# 5vTemp.net
KiCad netlist of a schematic drawn in EAGLE
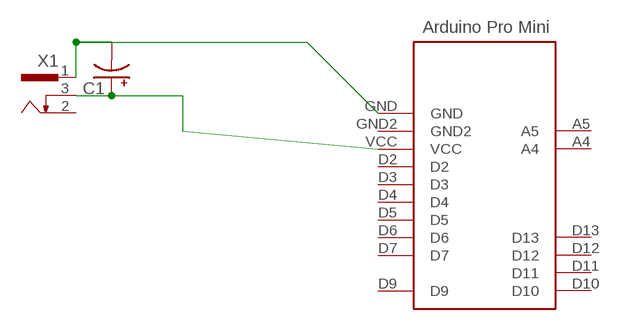
[diagram p0: schematic, sheet 1]

(export (version "E")
  (design (tool "Eeschema 10.0.6"))
  (components
    (comp (ref "C1")
      (value "CPOL-USSANYO_C")
      (footprint "eagle-import:SANYO-OSCON_C")
      (libsource (lib "eagle-import") (part "CPOL-USSANYO_C"))
    )
    (comp (ref "U$1")
      (value "ARDUINO_PRO_MINI_5V_V2V2")
      (footprint "eagle-import:ARDUINO_PRO_MINI_5V_V2")
      (libsource (lib "eagle-import") (part "ARDUINO_PRO_MINI_5V_V2V2"))
    )
    (comp (ref "X1")
      (value "733980-62")
      (footprint "eagle-import:733980-62")
      (libsource (lib "eagle-import") (part "73398?0-62"))
    )
  )
  (nets
    (net (code "1") (name "Net-(C1-Pad+)") (class "Default")
      (node (ref "C1") (pin "+") (pinfunction "+_+") (pintype "passive"))
      (node (ref "U$1") (pin "VCC") (pinfunction "VCC_VCC") (pintype "bidirectional"))
      (node (ref "X1") (pin "3") (pinfunction "3_3") (pintype "passive"))
    )
    (net (code "2") (name "Net-(C1-Pad-)") (class "Default")
      (node (ref "C1") (pin "-") (pinfunction "-_-") (pintype "passive"))
      (node (ref "U$1") (pin "GND") (pinfunction "GND_GND") (pintype "bidirectional"))
      (node (ref "X1") (pin "1") (pinfunction "1_1") (pintype "passive"))
    )
    (net (code "3") (name "unconnected-(U$1-PadA4)") (class "Default")
      (node (ref "U$1") (pin "A4") (pinfunction "A4_A4") (pintype "bidirectional"))
    )
    (net (code "4") (name "unconnected-(U$1-PadA5)") (class "Default")
      (node (ref "U$1") (pin "A5") (pinfunction "A5_A5") (pintype "bidirectional"))
    )
    (net (code "5") (name "unconnected-(U$1-PadD2)") (class "Default")
      (node (ref "U$1") (pin "D2") (pinfunction "D2_D2") (pintype "bidirectional"))
    )
    (net (code "6") (name "unconnected-(U$1-PadD3)") (class "Default")
      (node (ref "U$1") (pin "D3") (pinfunction "D3_D3") (pintype "bidirectional"))
    )
    (net (code "7") (name "unconnected-(U$1-PadD4)") (class "Default")
      (node (ref "U$1") (pin "D4") (pinfunction "D4_D4") (pintype "bidirectional"))
    )
    (net (code "8") (name "unconnected-(U$1-PadD5)") (class "Default")
      (node (ref "U$1") (pin "D5") (pinfunction "D5_D5") (pintype "bidirectional"))
    )
    (net (code "9") (name "unconnected-(U$1-PadD6)") (class "Default")
      (node (ref "U$1") (pin "D6") (pinfunction "D6_D6") (pintype "bidirectional"))
    )
    (net (code "10") (name "unconnected-(U$1-PadD7)") (class "Default")
      (node (ref "U$1") (pin "D7") (pinfunction "D7_D7") (pintype "bidirectional"))
    )
    (net (code "11") (name "unconnected-(U$1-PadD9)") (class "Default")
      (node (ref "U$1") (pin "D9") (pinfunction "D9_D9") (pintype "bidirectional"))
    )
    (net (code "12") (name "unconnected-(U$1-PadD10)") (class "Default")
      (node (ref "U$1") (pin "D10") (pinfunction "D10_D10") (pintype "bidirectional"))
    )
    (net (code "13") (name "unconnected-(U$1-PadD11)") (class "Default")
      (node (ref "U$1") (pin "D11") (pinfunction "D11_D11") (pintype "bidirectional"))
    )
    (net (code "14") (name "unconnected-(U$1-PadD12)") (class "Default")
      (node (ref "U$1") (pin "D12") (pinfunction "D12_D12") (pintype "bidirectional"))
    )
    (net (code "15") (name "unconnected-(U$1-PadD13)") (class "Default")
      (node (ref "U$1") (pin "D13") (pinfunction "D13_D13") (pintype "bidirectional"))
    )
    (net (code "16") (name "unconnected-(U$1-PadGND2)") (class "Default")
      (node (ref "U$1") (pin "GND2") (pinfunction "GND2_GND2") (pintype "bidirectional"))
    )
    (net (code "17") (name "unconnected-(X1-Pad2)") (class "Default")
      (node (ref "X1") (pin "2") (pinfunction "2_2") (pintype "passive"))
    )
  )
)
